# latch7.net
KiCad netlist of a schematic drawn in EAGLE
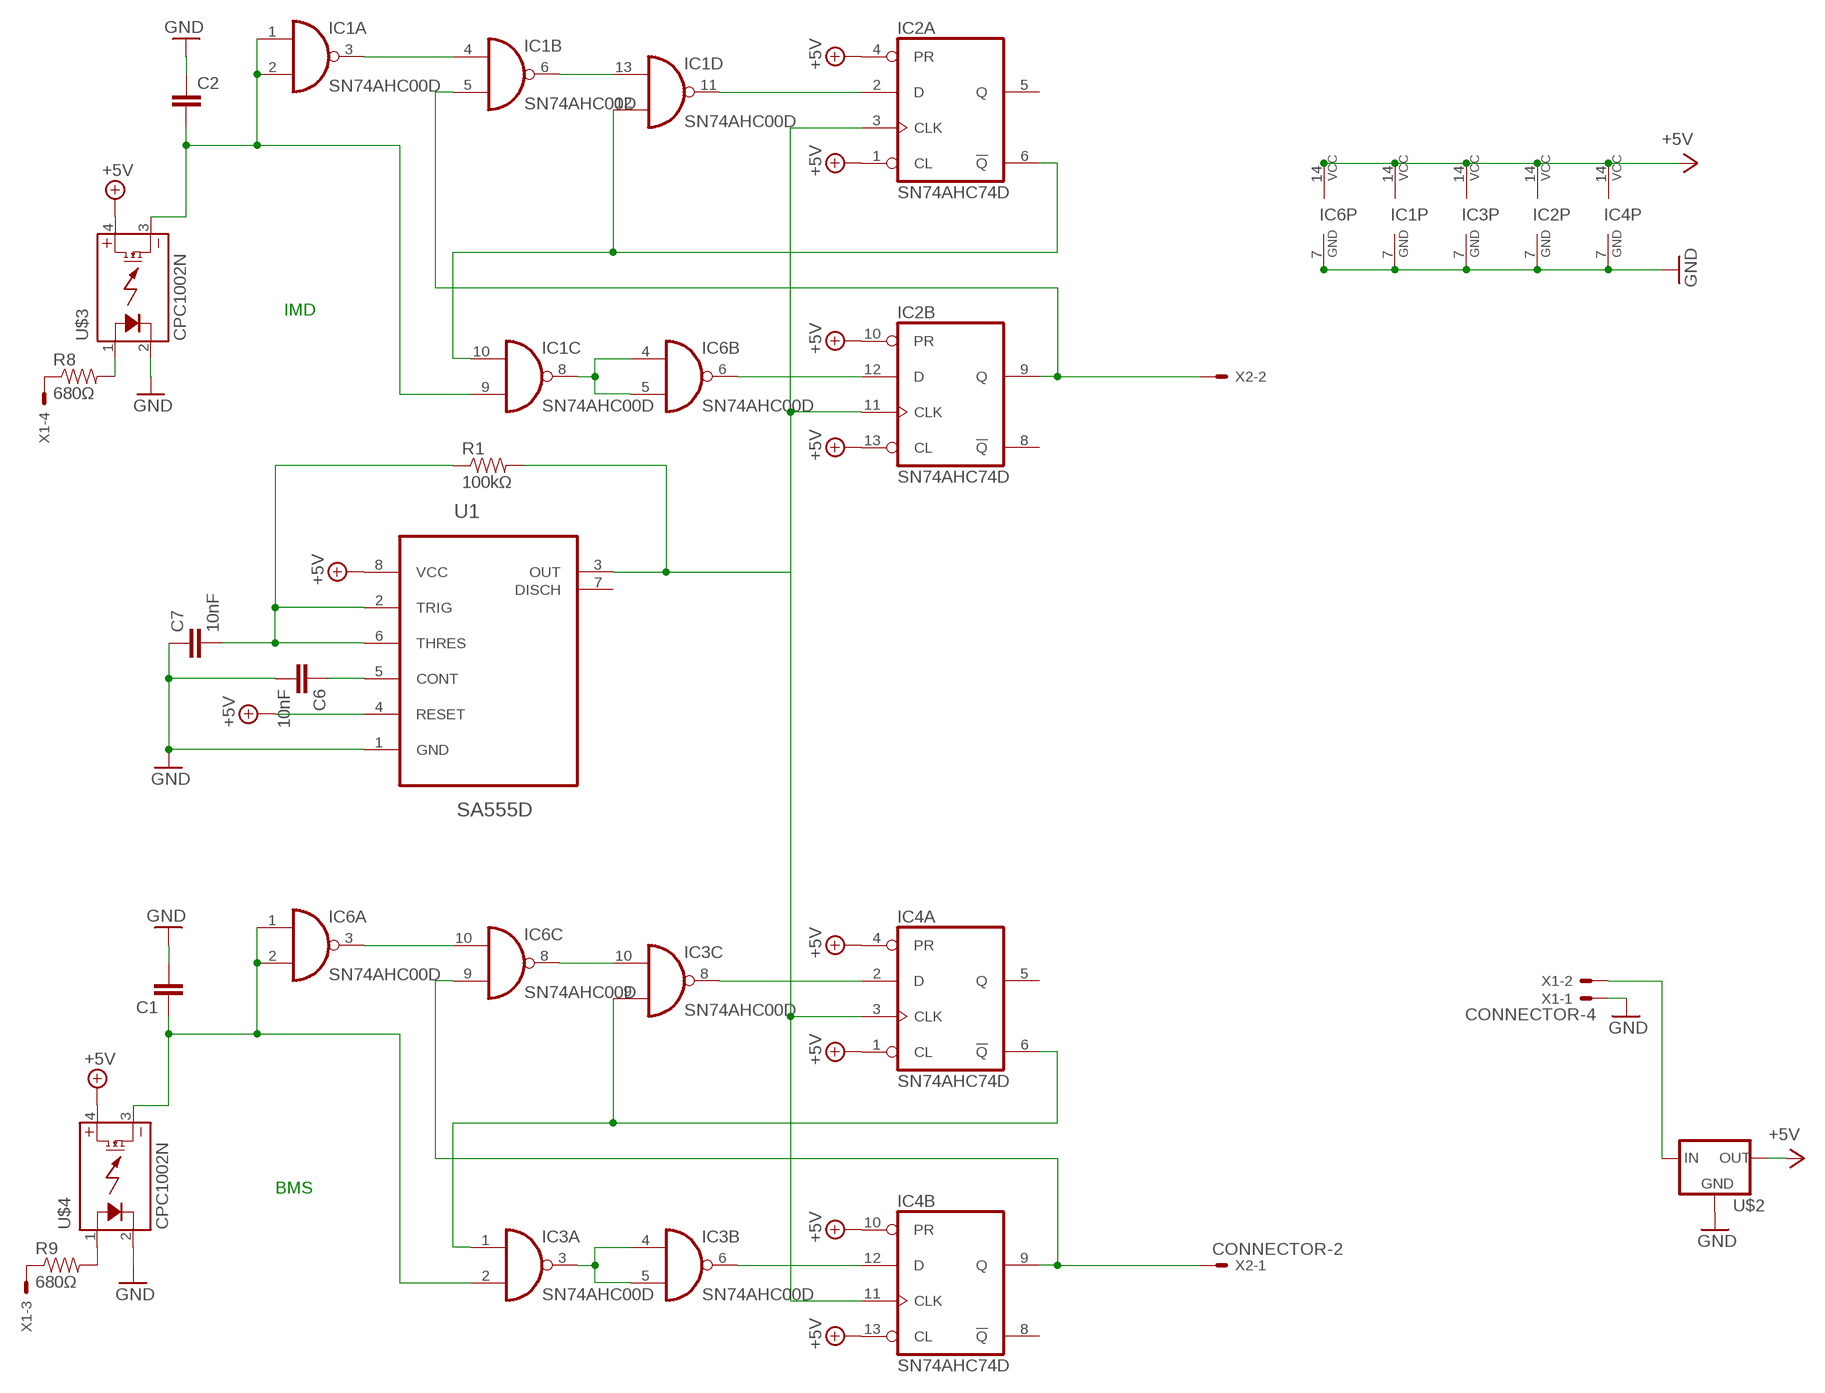
[diagram p0: schematic, sheet 1]

(export (version "E")
  (design (tool "Eeschema 10.0.6"))
  (components
    (comp (ref "C1")
      (value "CAP0402-CAP")
      (footprint "eagle-import:0402-CAP")
      (libsource (lib "eagle-import") (part "CAP0402-CAP"))
    )
    (comp (ref "C2")
      (value "CAP0402-CAP")
      (footprint "eagle-import:0402-CAP")
      (libsource (lib "eagle-import") (part "CAP0402-CAP"))
    )
    (comp (ref "C6")
      (value "10nF")
      (footprint "eagle-import:0402-CAP")
      (libsource (lib "eagle-import") (part "CAP0402-CAP"))
    )
    (comp (ref "C7")
      (value "10nF")
      (footprint "eagle-import:0402-CAP")
      (libsource (lib "eagle-import") (part "CAP0402-CAP"))
    )
    (comp (ref "IC1")
      (value "SN74AHC00D")
      (footprint "eagle-import:SOIC-14")
      (libsource (lib "eagle-import") (part "SN74AHC00D"))
    )
    (comp (ref "IC2")
      (value "SN74AHC74D")
      (footprint "eagle-import:SOIC-14")
      (libsource (lib "eagle-import") (part "SN74AHC74D"))
    )
    (comp (ref "IC3")
      (value "SN74AHC00D")
      (footprint "eagle-import:SOIC-14")
      (libsource (lib "eagle-import") (part "SN74AHC00D"))
    )
    (comp (ref "IC4")
      (value "SN74AHC74D")
      (footprint "eagle-import:SOIC-14")
      (libsource (lib "eagle-import") (part "SN74AHC74D"))
    )
    (comp (ref "IC6")
      (value "SN74AHC00D")
      (footprint "eagle-import:SOIC-14")
      (libsource (lib "eagle-import") (part "SN74AHC00D"))
    )
    (comp (ref "R1")
      (value "100kΩ")
      (footprint "eagle-import:0402-RES")
      (libsource (lib "eagle-import") (part "RESISTOR0402"))
    )
    (comp (ref "R8")
      (value "680Ω")
      (footprint "eagle-import:0402-RES")
      (libsource (lib "eagle-import") (part "RESISTOR0402"))
    )
    (comp (ref "R9")
      (value "680Ω")
      (footprint "eagle-import:0402-RES")
      (libsource (lib "eagle-import") (part "RESISTOR0402"))
    )
    (comp (ref "U$2")
      (value "5VREG_LM340-NLM340MPX-5.0/NOPB")
      (footprint "eagle-import:SOT223")
      (libsource (lib "eagle-import") (part "5VREG_LM340-NLM340MPX-5.0/NOPB"))
    )
    (comp (ref "U$3")
      (value "CPC1002N")
      (footprint "eagle-import:SOP04")
      (libsource (lib "eagle-import") (part "CPC1002N"))
    )
    (comp (ref "U$4")
      (value "CPC1002N")
      (footprint "eagle-import:SOP04")
      (libsource (lib "eagle-import") (part "CPC1002N"))
    )
    (comp (ref "U1")
      (value "SA555D")
      (footprint "eagle-import:SOIC127P600X175-8N")
      (libsource (lib "eagle-import") (part "SA555D"))
    )
    (comp (ref "X1")
      (value "CONNECTOR-4")
      (footprint "eagle-import:MINIFIT_5566-4")
      (libsource (lib "eagle-import") (part "CONNECTOR-4"))
    )
    (comp (ref "X2")
      (value "CONNECTOR-2")
      (footprint "eagle-import:MINIFIT_5566-2")
      (libsource (lib "eagle-import") (part "CONNECTOR-2"))
    )
  )
  (nets
    (net (code "1") (name "+5V") (class "Default")
      (node (ref "IC1") (pin "14") (pinfunction "VCC_14") (pintype "power_in"))
      (node (ref "IC2") (pin "1") (pinfunction "CL_1") (pintype "input"))
      (node (ref "IC2") (pin "10") (pinfunction "PR_10") (pintype "input"))
      (node (ref "IC2") (pin "13") (pinfunction "CL_13") (pintype "input"))
      (node (ref "IC2") (pin "14") (pinfunction "VCC_14") (pintype "power_in"))
      (node (ref "IC2") (pin "4") (pinfunction "PR_4") (pintype "input"))
      (node (ref "IC3") (pin "14") (pinfunction "VCC_14") (pintype "power_in"))
      (node (ref "IC4") (pin "1") (pinfunction "CL_1") (pintype "input"))
      (node (ref "IC4") (pin "10") (pinfunction "PR_10") (pintype "input"))
      (node (ref "IC4") (pin "13") (pinfunction "CL_13") (pintype "input"))
      (node (ref "IC4") (pin "14") (pinfunction "VCC_14") (pintype "power_in"))
      (node (ref "IC4") (pin "4") (pinfunction "PR_4") (pintype "input"))
      (node (ref "IC6") (pin "14") (pinfunction "VCC_14") (pintype "power_in"))
      (node (ref "U$2") (pin "3") (pinfunction "OUT_3") (pintype "output"))
      (node (ref "U$3") (pin "4") (pinfunction "DC+_4") (pintype "passive"))
      (node (ref "U$4") (pin "4") (pinfunction "DC+_4") (pintype "passive"))
      (node (ref "U1") (pin "4") (pinfunction "RESET_4") (pintype "input"))
      (node (ref "U1") (pin "8") (pinfunction "VCC_8") (pintype "power_in"))
    )
    (net (code "2") (name "GND") (class "Default")
      (node (ref "C1") (pin "2") (pinfunction "2_2") (pintype "passive"))
      (node (ref "C2") (pin "1") (pinfunction "1_1") (pintype "passive"))
      (node (ref "C6") (pin "2") (pinfunction "2_2") (pintype "passive"))
      (node (ref "C7") (pin "1") (pinfunction "1_1") (pintype "passive"))
      (node (ref "IC1") (pin "7") (pinfunction "GND_7") (pintype "power_in"))
      (node (ref "IC2") (pin "7") (pinfunction "GND_7") (pintype "power_in"))
      (node (ref "IC3") (pin "7") (pinfunction "GND_7") (pintype "power_in"))
      (node (ref "IC4") (pin "7") (pinfunction "GND_7") (pintype "power_in"))
      (node (ref "IC6") (pin "7") (pinfunction "GND_7") (pintype "power_in"))
      (node (ref "U$2") (pin "2") (pinfunction "GND_2") (pintype "input"))
      (node (ref "U$2") (pin "4") (pinfunction "GND_4") (pintype "input"))
      (node (ref "U$3") (pin "2") (pinfunction "CONTROL-_2") (pintype "passive"))
      (node (ref "U$4") (pin "2") (pinfunction "CONTROL-_2") (pintype "passive"))
      (node (ref "U1") (pin "1") (pinfunction "GND_1") (pintype "passive"))
      (node (ref "X1") (pin "1") (pinfunction "S_1") (pintype "passive"))
    )
    (net (code "3") (name "Net-(IC1A-I0)") (class "Default")
      (node (ref "C2") (pin "2") (pinfunction "2_2") (pintype "passive"))
      (node (ref "IC1") (pin "1") (pinfunction "I0_1") (pintype "input"))
      (node (ref "IC1") (pin "2") (pinfunction "I1_2") (pintype "input"))
      (node (ref "IC1") (pin "9") (pinfunction "I1_9") (pintype "input"))
      (node (ref "U$3") (pin "3") (pinfunction "DC-_3") (pintype "passive"))
    )
    (net (code "4") (name "Net-(IC1A-O)") (class "Default")
      (node (ref "IC1") (pin "3") (pinfunction "O_3") (pintype "output"))
      (node (ref "IC1") (pin "4") (pinfunction "I0_4") (pintype "input"))
    )
    (net (code "5") (name "Net-(IC1B-I1)") (class "Default")
      (node (ref "IC1") (pin "5") (pinfunction "I1_5") (pintype "input"))
      (node (ref "IC2") (pin "9") (pinfunction "Q_9") (pintype "output"))
      (node (ref "X2") (pin "2") (pinfunction "S_2") (pintype "passive"))
    )
    (net (code "6") (name "Net-(IC1B-O)") (class "Default")
      (node (ref "IC1") (pin "13") (pinfunction "I0_13") (pintype "input"))
      (node (ref "IC1") (pin "6") (pinfunction "O_6") (pintype "output"))
    )
    (net (code "7") (name "Net-(IC1C-I0)") (class "Default")
      (node (ref "IC1") (pin "10") (pinfunction "I0_10") (pintype "input"))
      (node (ref "IC1") (pin "12") (pinfunction "I1_12") (pintype "input"))
      (node (ref "IC2") (pin "6") (pinfunction "~{Q}_6") (pintype "output"))
    )
    (net (code "8") (name "Net-(IC1C-O)") (class "Default")
      (node (ref "IC1") (pin "8") (pinfunction "O_8") (pintype "output"))
      (node (ref "IC6") (pin "4") (pinfunction "I0_4") (pintype "input"))
      (node (ref "IC6") (pin "5") (pinfunction "I1_5") (pintype "input"))
    )
    (net (code "9") (name "Net-(IC1D-O)") (class "Default")
      (node (ref "IC1") (pin "11") (pinfunction "O_11") (pintype "output"))
      (node (ref "IC2") (pin "2") (pinfunction "D_2") (pintype "input"))
    )
    (net (code "10") (name "Net-(IC2A-CLK)") (class "Default")
      (node (ref "IC2") (pin "11") (pinfunction "CLK_11") (pintype "input"))
      (node (ref "IC2") (pin "3") (pinfunction "CLK_3") (pintype "input"))
      (node (ref "IC4") (pin "11") (pinfunction "CLK_11") (pintype "input"))
      (node (ref "IC4") (pin "3") (pinfunction "CLK_3") (pintype "input"))
      (node (ref "R1") (pin "2") (pinfunction "2_2") (pintype "passive"))
      (node (ref "U1") (pin "3") (pinfunction "OUT_3") (pintype "output"))
    )
    (net (code "11") (name "Net-(IC2B-D)") (class "Default")
      (node (ref "IC2") (pin "12") (pinfunction "D_12") (pintype "input"))
      (node (ref "IC6") (pin "6") (pinfunction "O_6") (pintype "output"))
    )
    (net (code "12") (name "Net-(IC3A-I0)") (class "Default")
      (node (ref "IC3") (pin "1") (pinfunction "I0_1") (pintype "input"))
      (node (ref "IC3") (pin "9") (pinfunction "I1_9") (pintype "input"))
      (node (ref "IC4") (pin "6") (pinfunction "~{Q}_6") (pintype "output"))
    )
    (net (code "13") (name "Net-(IC3A-I1)") (class "Default")
      (node (ref "C1") (pin "1") (pinfunction "1_1") (pintype "passive"))
      (node (ref "IC3") (pin "2") (pinfunction "I1_2") (pintype "input"))
      (node (ref "IC6") (pin "1") (pinfunction "I0_1") (pintype "input"))
      (node (ref "IC6") (pin "2") (pinfunction "I1_2") (pintype "input"))
      (node (ref "U$4") (pin "3") (pinfunction "DC-_3") (pintype "passive"))
    )
    (net (code "14") (name "Net-(IC3A-O)") (class "Default")
      (node (ref "IC3") (pin "3") (pinfunction "O_3") (pintype "output"))
      (node (ref "IC3") (pin "4") (pinfunction "I0_4") (pintype "input"))
      (node (ref "IC3") (pin "5") (pinfunction "I1_5") (pintype "input"))
    )
    (net (code "15") (name "Net-(IC3B-O)") (class "Default")
      (node (ref "IC3") (pin "6") (pinfunction "O_6") (pintype "output"))
      (node (ref "IC4") (pin "12") (pinfunction "D_12") (pintype "input"))
    )
    (net (code "16") (name "Net-(IC3C-I0)") (class "Default")
      (node (ref "IC3") (pin "10") (pinfunction "I0_10") (pintype "input"))
      (node (ref "IC6") (pin "8") (pinfunction "O_8") (pintype "output"))
    )
    (net (code "17") (name "Net-(IC3C-O)") (class "Default")
      (node (ref "IC3") (pin "8") (pinfunction "O_8") (pintype "output"))
      (node (ref "IC4") (pin "2") (pinfunction "D_2") (pintype "input"))
    )
    (net (code "18") (name "Net-(IC4B-Q)") (class "Default")
      (node (ref "IC4") (pin "9") (pinfunction "Q_9") (pintype "output"))
      (node (ref "IC6") (pin "9") (pinfunction "I1_9") (pintype "input"))
      (node (ref "X2") (pin "1") (pinfunction "S_1") (pintype "passive"))
    )
    (net (code "19") (name "Net-(IC6A-O)") (class "Default")
      (node (ref "IC6") (pin "10") (pinfunction "I0_10") (pintype "input"))
      (node (ref "IC6") (pin "3") (pinfunction "O_3") (pintype "output"))
    )
    (net (code "20") (name "Net-(U$2-IN)") (class "Default")
      (node (ref "U$2") (pin "1") (pinfunction "IN_1") (pintype "input"))
      (node (ref "X1") (pin "2") (pinfunction "S_2") (pintype "passive"))
    )
    (net (code "21") (name "Net-(U$3-CONTROL+)") (class "Default")
      (node (ref "R8") (pin "2") (pinfunction "2_2") (pintype "passive"))
      (node (ref "U$3") (pin "1") (pinfunction "CONTROL+_1") (pintype "passive"))
    )
    (net (code "22") (name "Net-(U$4-CONTROL+)") (class "Default")
      (node (ref "R9") (pin "2") (pinfunction "2_2") (pintype "passive"))
      (node (ref "U$4") (pin "1") (pinfunction "CONTROL+_1") (pintype "passive"))
    )
    (net (code "23") (name "Net-(U1-CONT)") (class "Default")
      (node (ref "C6") (pin "1") (pinfunction "1_1") (pintype "passive"))
      (node (ref "U1") (pin "5") (pinfunction "CONT_5") (pintype "input"))
    )
    (net (code "24") (name "Net-(U1-THRES)") (class "Default")
      (node (ref "C7") (pin "2") (pinfunction "2_2") (pintype "passive"))
      (node (ref "R1") (pin "1") (pinfunction "1_1") (pintype "passive"))
      (node (ref "U1") (pin "2") (pinfunction "TRIG_2") (pintype "input"))
      (node (ref "U1") (pin "6") (pinfunction "THRES_6") (pintype "input"))
    )
    (net (code "25") (name "Net-(X1C-S)") (class "Default")
      (node (ref "R9") (pin "1") (pinfunction "1_1") (pintype "passive"))
      (node (ref "X1") (pin "3") (pinfunction "S_3") (pintype "passive"))
    )
    (net (code "26") (name "Net-(X1D-S)") (class "Default")
      (node (ref "R8") (pin "1") (pinfunction "1_1") (pintype "passive"))
      (node (ref "X1") (pin "4") (pinfunction "S_4") (pintype "passive"))
    )
    (net (code "27") (name "unconnected-(IC2A-Q-Pad5)") (class "Default")
      (node (ref "IC2") (pin "5") (pinfunction "Q_5") (pintype "output"))
    )
    (net (code "28") (name "unconnected-(IC2B-~{Q}-Pad8)") (class "Default")
      (node (ref "IC2") (pin "8") (pinfunction "~{Q}_8") (pintype "output"))
    )
    (net (code "29") (name "unconnected-(IC4A-Q-Pad5)") (class "Default")
      (node (ref "IC4") (pin "5") (pinfunction "Q_5") (pintype "output"))
    )
    (net (code "30") (name "unconnected-(IC4B-~{Q}-Pad8)") (class "Default")
      (node (ref "IC4") (pin "8") (pinfunction "~{Q}_8") (pintype "output"))
    )
    (net (code "31") (name "unconnected-(U1-DISCH-Pad7)") (class "Default")
      (node (ref "U1") (pin "7") (pinfunction "DISCH_7") (pintype "output"))
    )
  )
)
